# Adafruit_protrinket_backpack.net
KiCad netlist of a schematic drawn in EAGLE
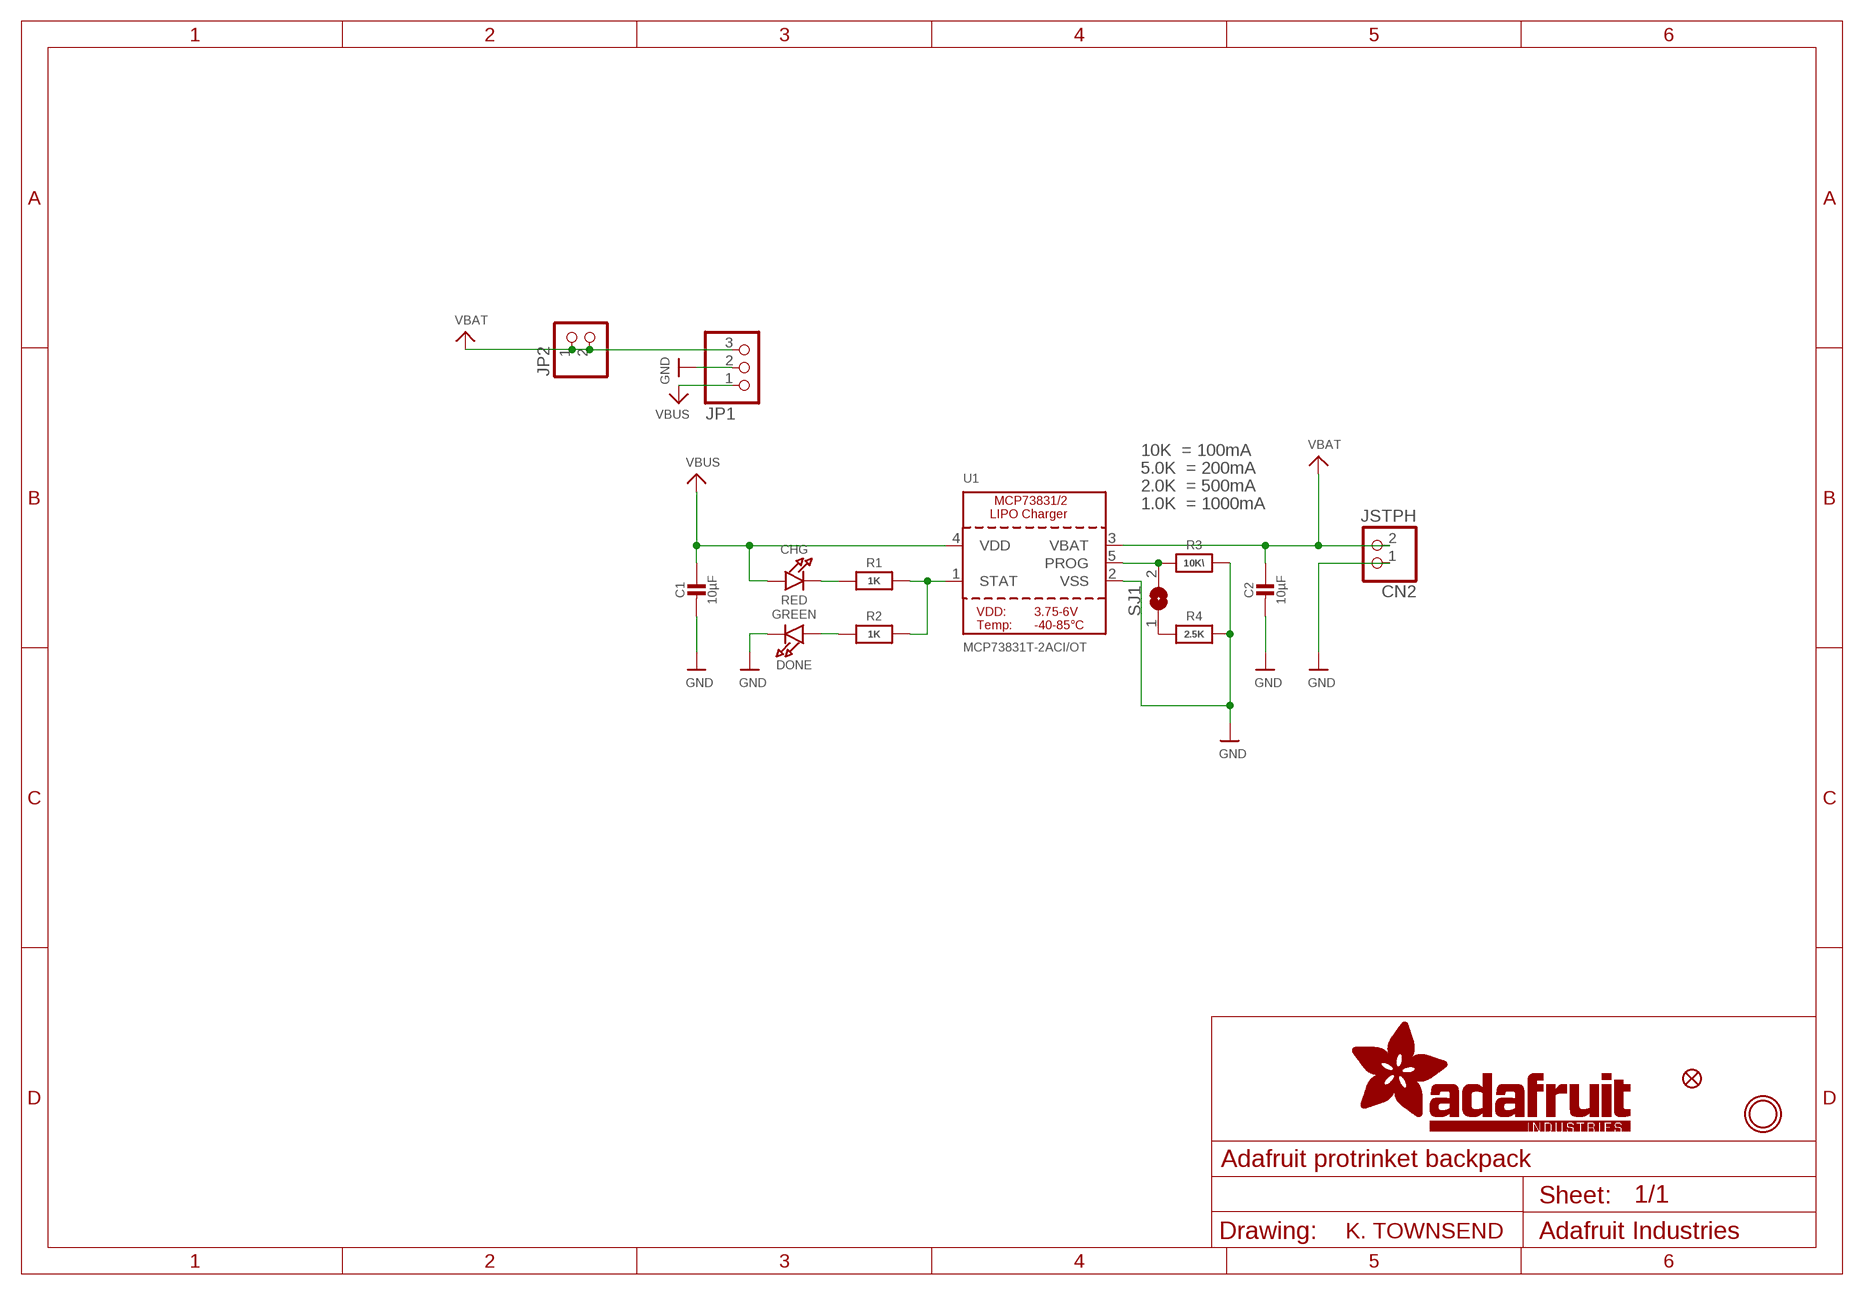
[diagram p0: schematic, sheet 1]

(export (version "E")
  (design (tool "Eeschema 10.0.6"))
  (components
    (comp (ref "C1")
      (value "10µF")
      (footprint "eagle-import:0805-NO")
      (libsource (lib "eagle-import") (part "CAP_CERAMIC0805-NOOUTLINE"))
    )
    (comp (ref "C2")
      (value "10µF")
      (footprint "eagle-import:0805-NO")
      (libsource (lib "eagle-import") (part "CAP_CERAMIC0805-NOOUTLINE"))
    )
    (comp (ref "CHG")
      (value "RED")
      (footprint "eagle-import:CHIPLED_0805_NOOUTLINE")
      (libsource (lib "eagle-import") (part "LED0805_NOOUTLINE"))
    )
    (comp (ref "CN2")
      (value "JSTPH")
      (footprint "eagle-import:JSTPH2")
      (libsource (lib "eagle-import") (part "JST_2PIN"))
    )
    (comp (ref "DONE")
      (value "GREEN")
      (footprint "eagle-import:CHIPLED_0805_NOOUTLINE")
      (libsource (lib "eagle-import") (part "LED0805_NOOUTLINE"))
    )
    (comp (ref "FID1")
      (value "FIDUCIAL\"\"")
      (footprint "eagle-import:FIDUCIAL_1MM")
      (libsource (lib "eagle-import") (part "FIDUCIAL{dblquote}{dblquote}"))
    )
    (comp (ref "JP1")
      (value "HEADER-1X376MIL")
      (footprint "eagle-import:1X03_ROUND_76")
      (libsource (lib "eagle-import") (part "HEADER-1X376MIL"))
    )
    (comp (ref "JP2")
      (value "HEADER-1X2ROUND")
      (footprint "eagle-import:1X02_ROUND")
      (libsource (lib "eagle-import") (part "HEADER-1X2ROUND"))
    )
    (comp (ref "R1")
      (value "1K")
      (footprint "eagle-import:0805-NO")
      (libsource (lib "eagle-import") (part "RESISTOR0805_NOOUTLINE"))
    )
    (comp (ref "R2")
      (value "1K")
      (footprint "eagle-import:0805-NO")
      (libsource (lib "eagle-import") (part "RESISTOR0805_NOOUTLINE"))
    )
    (comp (ref "R3")
      (value "10K\\")
      (footprint "eagle-import:_0805MP")
      (libsource (lib "eagle-import") (part "RESISTOR_0805MP"))
    )
    (comp (ref "R4")
      (value "2.5K")
      (footprint "eagle-import:0805-NO")
      (libsource (lib "eagle-import") (part "RESISTOR0805_NOOUTLINE"))
    )
    (comp (ref "SJ1")
      (value "SOLDERJUMPER")
      (footprint "eagle-import:SOLDERJUMPER_ARROW_NOPASTE")
      (libsource (lib "eagle-import") (part "SOLDERJUMPER"))
    )
    (comp (ref "U$10")
      (value "MOUNTINGHOLE2.5")
      (footprint "eagle-import:MOUNTINGHOLE_2.5_PLATED")
      (libsource (lib "eagle-import") (part "MOUNTINGHOLE2.5"))
    )
    (comp (ref "U1")
      (value "MCP73831T-2ACI/OT")
      (footprint "eagle-import:SOT23-5")
      (libsource (lib "eagle-import") (part "MCP73831/2"))
    )
  )
  (nets
    (net (code "1") (name "GND") (class "Default")
      (node (ref "C1") (pin "2") (pinfunction "2_2") (pintype "passive"))
      (node (ref "C2") (pin "2") (pinfunction "2_2") (pintype "passive"))
      (node (ref "CN2") (pin "1") (pinfunction "1_1") (pintype "passive"))
      (node (ref "DONE") (pin "C") (pinfunction "C_C") (pintype "passive"))
      (node (ref "JP1") (pin "2") (pinfunction "2_2") (pintype "passive"))
      (node (ref "R3") (pin "2") (pinfunction "2_2") (pintype "passive"))
      (node (ref "R4") (pin "2") (pinfunction "2_2") (pintype "passive"))
      (node (ref "U1") (pin "2") (pinfunction "VSS_2") (pintype "power_in"))
    )
    (net (code "2") (name "Net-(CHG-PadC)") (class "Default")
      (node (ref "CHG") (pin "C") (pinfunction "C_C") (pintype "passive"))
      (node (ref "R1") (pin "1") (pinfunction "1_1") (pintype "passive"))
    )
    (net (code "3") (name "Net-(DONE-PadA)") (class "Default")
      (node (ref "DONE") (pin "A") (pinfunction "A_A") (pintype "passive"))
      (node (ref "R2") (pin "1") (pinfunction "1_1") (pintype "passive"))
    )
    (net (code "4") (name "Net-(R4-Pad1)") (class "Default")
      (node (ref "R4") (pin "1") (pinfunction "1_1") (pintype "passive"))
      (node (ref "SJ1") (pin "1") (pinfunction "1_1") (pintype "passive"))
    )
    (net (code "5") (name "Net-(U1-PROG)") (class "Default")
      (node (ref "R3") (pin "1") (pinfunction "1_1") (pintype "passive"))
      (node (ref "SJ1") (pin "2") (pinfunction "2_2") (pintype "passive"))
      (node (ref "U1") (pin "5") (pinfunction "PROG_5") (pintype "input"))
    )
    (net (code "6") (name "Net-(U1-STAT)") (class "Default")
      (node (ref "R1") (pin "2") (pinfunction "2_2") (pintype "passive"))
      (node (ref "R2") (pin "2") (pinfunction "2_2") (pintype "passive"))
      (node (ref "U1") (pin "1") (pinfunction "STAT_1") (pintype "output"))
    )
    (net (code "7") (name "VBAT") (class "Default")
      (node (ref "C2") (pin "1") (pinfunction "1_1") (pintype "passive"))
      (node (ref "CN2") (pin "2") (pinfunction "2_2") (pintype "passive"))
      (node (ref "JP1") (pin "3") (pinfunction "3_3") (pintype "passive"))
      (node (ref "JP2") (pin "1") (pinfunction "1_1") (pintype "passive"))
      (node (ref "JP2") (pin "2") (pinfunction "2_2") (pintype "passive"))
      (node (ref "U1") (pin "3") (pinfunction "VBAT_3") (pintype "power_in"))
    )
    (net (code "8") (name "VBUS") (class "Default")
      (node (ref "C1") (pin "1") (pinfunction "1_1") (pintype "passive"))
      (node (ref "CHG") (pin "A") (pinfunction "A_A") (pintype "passive"))
      (node (ref "JP1") (pin "1") (pinfunction "1_1") (pintype "passive"))
      (node (ref "U1") (pin "4") (pinfunction "VDD_4") (pintype "power_in"))
    )
  )
)
